# TSOC_GROVEY_I2CHUB_R2_1.net
KiCad netlist of a schematic drawn in EAGLE
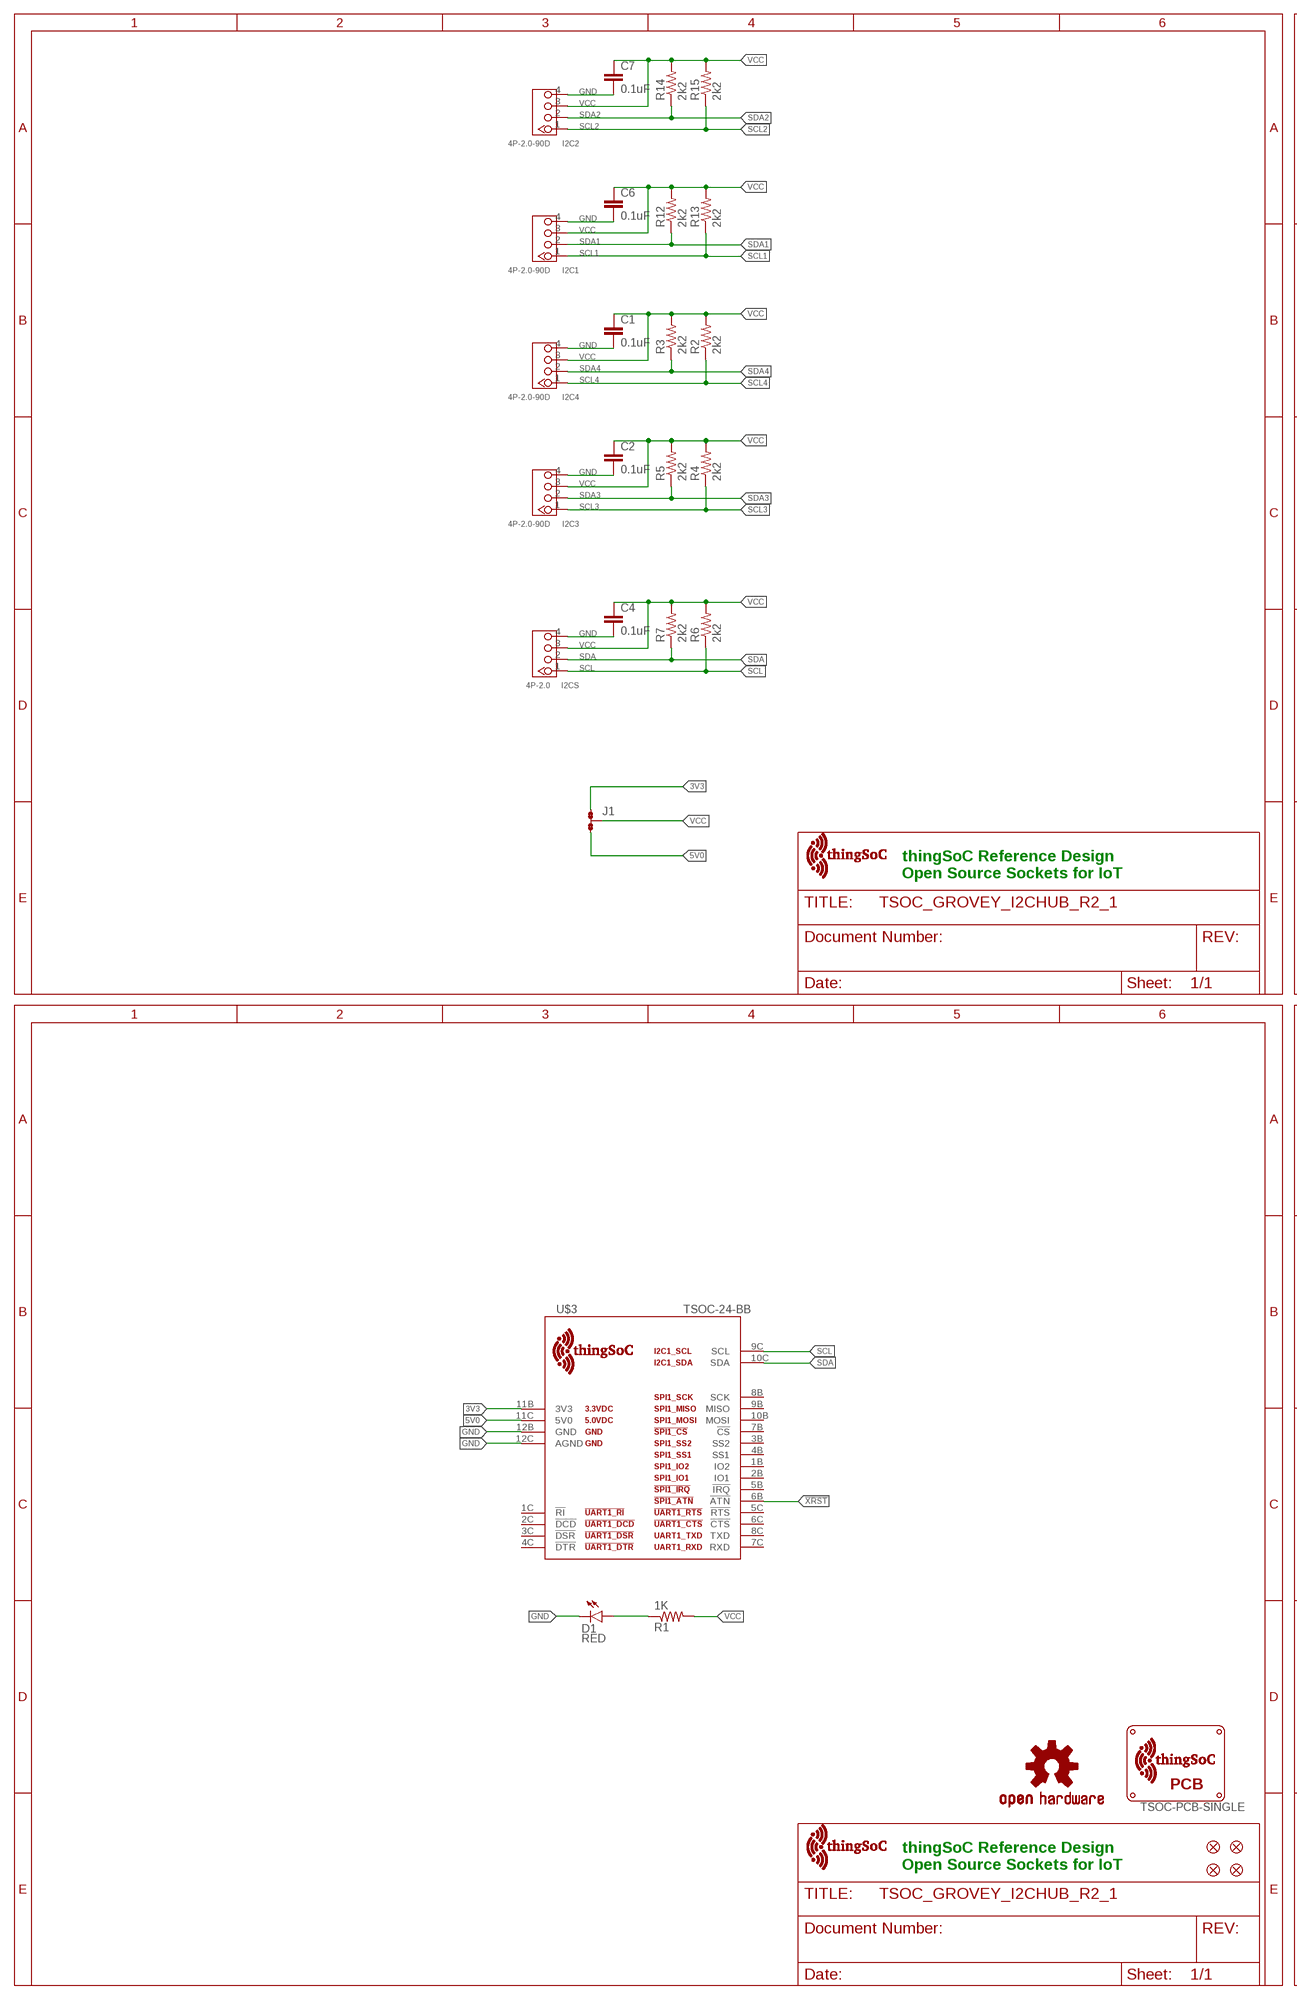
[diagram p0: schematic, sheet 1, part 1 of 2]
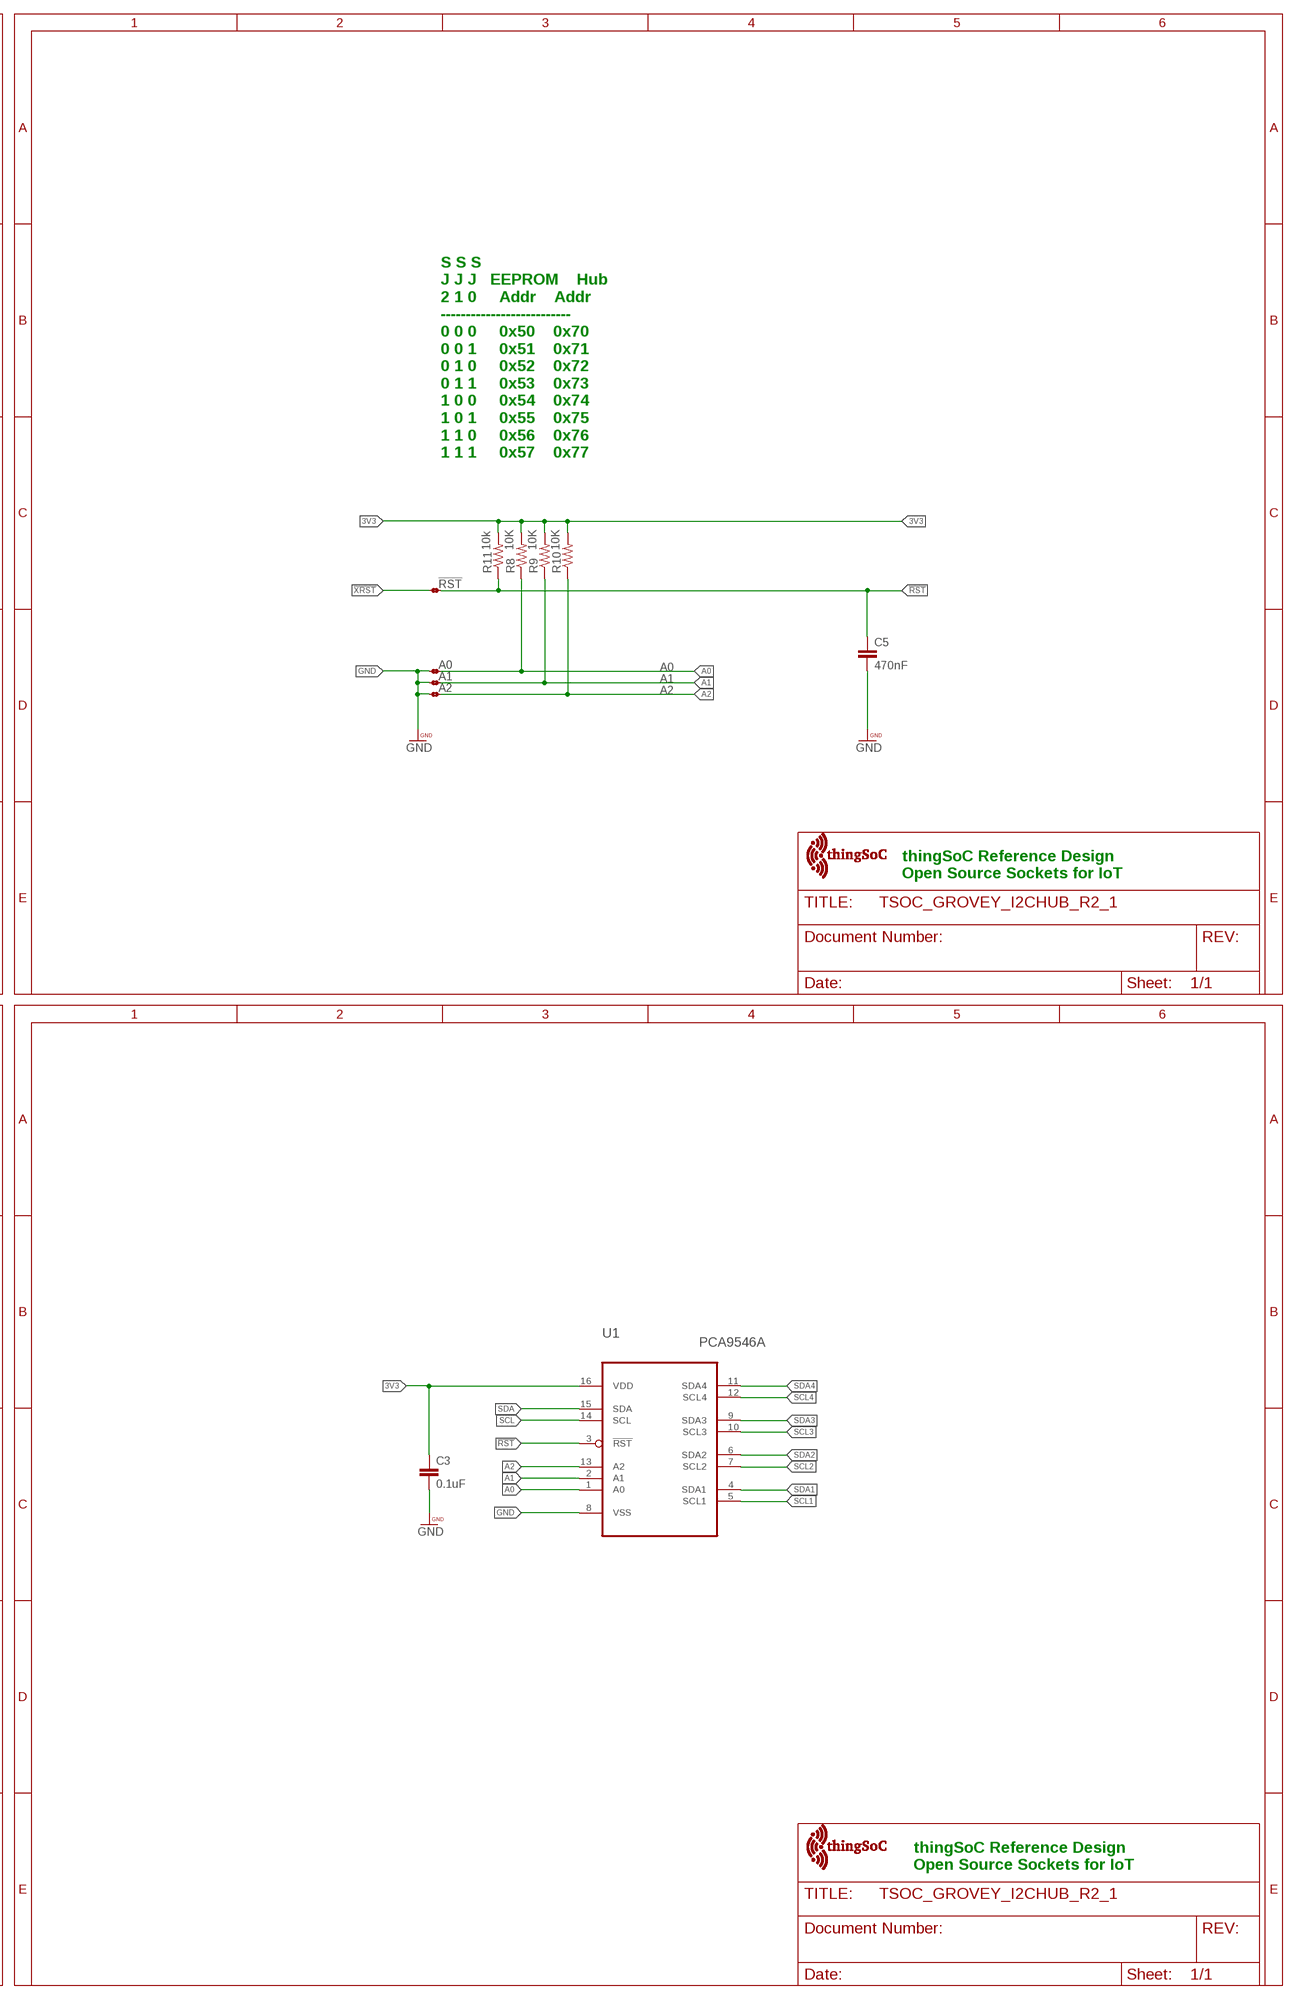
[diagram p1: schematic, sheet 1, part 2 of 2]

(export (version "E")
  (design (tool "Eeschema 10.0.6"))
  (components
    (comp (ref "!RST")
      (value "NO")
      (footprint "eagle-import:JMP-2-NO")
      (libsource (lib "eagle-import") (part "JMP-2-NO"))
    )
    (comp (ref "A0")
      (value "NO")
      (footprint "eagle-import:JMP-2-NO")
      (libsource (lib "eagle-import") (part "JMP-2-NO"))
    )
    (comp (ref "A1")
      (value "NO")
      (footprint "eagle-import:JMP-2-NO")
      (libsource (lib "eagle-import") (part "JMP-2-NO"))
    )
    (comp (ref "A2")
      (value "NO")
      (footprint "eagle-import:JMP-2-NO")
      (libsource (lib "eagle-import") (part "JMP-2-NO"))
    )
    (comp (ref "C1")
      (value "0.1uF")
      (footprint "eagle-import:0603-CAP")
      (libsource (lib "eagle-import") (part "CAP0603-CAP"))
    )
    (comp (ref "C2")
      (value "0.1uF")
      (footprint "eagle-import:0603-CAP")
      (libsource (lib "eagle-import") (part "CAP0603-CAP"))
    )
    (comp (ref "C3")
      (value "0.1uF")
      (footprint "eagle-import:0603-CAP")
      (libsource (lib "eagle-import") (part "CAP0603-CAP"))
    )
    (comp (ref "C4")
      (value "0.1uF")
      (footprint "eagle-import:0603-CAP")
      (libsource (lib "eagle-import") (part "CAP0603-CAP"))
    )
    (comp (ref "C5")
      (value "470nF")
      (footprint "eagle-import:0603-CAP")
      (libsource (lib "eagle-import") (part "CAP0603-CAP"))
    )
    (comp (ref "C6")
      (value "0.1uF")
      (footprint "eagle-import:0603-CAP")
      (libsource (lib "eagle-import") (part "CAP0603-CAP"))
    )
    (comp (ref "C7")
      (value "0.1uF")
      (footprint "eagle-import:0603-CAP")
      (libsource (lib "eagle-import") (part "CAP0603-CAP"))
    )
    (comp (ref "D1")
      (value "RED")
      (footprint "eagle-import:LED-0603")
      (libsource (lib "eagle-import") (part "LED0603"))
    )
    (comp (ref "FID1")
      (value "FIDUCIALUFIDUCIAL")
      (footprint "eagle-import:MICRO-FIDUCIAL")
      (libsource (lib "eagle-import") (part "FIDUCIALUFIDUCIAL"))
    )
    (comp (ref "FID2")
      (value "FIDUCIALUFIDUCIAL")
      (footprint "eagle-import:MICRO-FIDUCIAL")
      (libsource (lib "eagle-import") (part "FIDUCIALUFIDUCIAL"))
    )
    (comp (ref "FID3")
      (value "FIDUCIALUFIDUCIAL")
      (footprint "eagle-import:MICRO-FIDUCIAL")
      (libsource (lib "eagle-import") (part "FIDUCIALUFIDUCIAL"))
    )
    (comp (ref "FID4")
      (value "FIDUCIALUFIDUCIAL")
      (footprint "eagle-import:MICRO-FIDUCIAL")
      (libsource (lib "eagle-import") (part "FIDUCIALUFIDUCIAL"))
    )
    (comp (ref "I2C1")
      (value "4P-2.0-90D")
      (footprint "eagle-import:HW4-2.0-90D")
      (libsource (lib "eagle-import") (part "GROVE-CONNECTOR-DIP-90D(4P-2.0)"))
    )
    (comp (ref "I2C2")
      (value "4P-2.0-90D")
      (footprint "eagle-import:HW4-2.0-90D")
      (libsource (lib "eagle-import") (part "GROVE-CONNECTOR-DIP-90D(4P-2.0)"))
    )
    (comp (ref "I2C3")
      (value "4P-2.0-90D")
      (footprint "eagle-import:HW4-2.0-90D")
      (libsource (lib "eagle-import") (part "GROVE-CONNECTOR-DIP-90D(4P-2.0)"))
    )
    (comp (ref "I2C4")
      (value "4P-2.0-90D")
      (footprint "eagle-import:HW4-2.0-90D")
      (libsource (lib "eagle-import") (part "GROVE-CONNECTOR-DIP-90D(4P-2.0)"))
    )
    (comp (ref "I2CS")
      (value "4P-2.0")
      (footprint "eagle-import:HW4-2.0")
      (libsource (lib "eagle-import") (part "GROVE-CONNECTOR-DIP(4P-2.0)"))
    )
    (comp (ref "J1")
      (value "NO")
      (footprint "eagle-import:JMP-3-NO-PTH-2.54")
      (libsource (lib "eagle-import") (part "JMP-3-NO-PTH"))
    )
    (comp (ref "LOGO1")
      (value "OSHW-LOGOL")
      (footprint "eagle-import:OSHW-LOGO-L")
      (libsource (lib "eagle-import") (part "OSHW-LOGOL"))
    )
    (comp (ref "R1")
      (value "1K")
      (footprint "eagle-import:0603-RES")
      (libsource (lib "eagle-import") (part "RESISTOR_SFE0603-RES"))
    )
    (comp (ref "R2")
      (value "2k2")
      (footprint "eagle-import:0603-RES")
      (libsource (lib "eagle-import") (part "RESISTOR0603-RES"))
    )
    (comp (ref "R3")
      (value "2k2")
      (footprint "eagle-import:0603-RES")
      (libsource (lib "eagle-import") (part "RESISTOR0603-RES"))
    )
    (comp (ref "R4")
      (value "2k2")
      (footprint "eagle-import:0603-RES")
      (libsource (lib "eagle-import") (part "RESISTOR0603-RES"))
    )
    (comp (ref "R5")
      (value "2k2")
      (footprint "eagle-import:0603-RES")
      (libsource (lib "eagle-import") (part "RESISTOR0603-RES"))
    )
    (comp (ref "R6")
      (value "2k2")
      (footprint "eagle-import:0603-RES")
      (libsource (lib "eagle-import") (part "RESISTOR0603-RES"))
    )
    (comp (ref "R7")
      (value "2k2")
      (footprint "eagle-import:0603-RES")
      (libsource (lib "eagle-import") (part "RESISTOR0603-RES"))
    )
    (comp (ref "R8")
      (value "10K")
      (footprint "eagle-import:0603-RES")
      (libsource (lib "eagle-import") (part "RESISTOR0603-RES"))
    )
    (comp (ref "R9")
      (value "10K")
      (footprint "eagle-import:0603-RES")
      (libsource (lib "eagle-import") (part "RESISTOR0603-RES"))
    )
    (comp (ref "R10")
      (value "10K")
      (footprint "eagle-import:0603-RES")
      (libsource (lib "eagle-import") (part "RESISTOR0603-RES"))
    )
    (comp (ref "R11")
      (value "10k")
      (footprint "eagle-import:0603-RES")
      (libsource (lib "eagle-import") (part "RESISTOR0603-RES"))
    )
    (comp (ref "R12")
      (value "2k2")
      (footprint "eagle-import:0603-RES")
      (libsource (lib "eagle-import") (part "RESISTOR0603-RES"))
    )
    (comp (ref "R13")
      (value "2k2")
      (footprint "eagle-import:0603-RES")
      (libsource (lib "eagle-import") (part "RESISTOR0603-RES"))
    )
    (comp (ref "R14")
      (value "2k2")
      (footprint "eagle-import:0603-RES")
      (libsource (lib "eagle-import") (part "RESISTOR0603-RES"))
    )
    (comp (ref "R15")
      (value "2k2")
      (footprint "eagle-import:0603-RES")
      (libsource (lib "eagle-import") (part "RESISTOR0603-RES"))
    )
    (comp (ref "U$1")
      (value "TSOC-LOGO-SMALL")
      (footprint "eagle-import:TSOC-LOGO-SML")
      (libsource (lib "eagle-import") (part "TSOC-LOGO-SMALL"))
    )
    (comp (ref "U$2")
      (value "TSOC-PCB-SINGLE")
      (footprint "eagle-import:TSOC-BB-BRD-DIM")
      (libsource (lib "eagle-import") (part "TSOC-PCB-SINGLE"))
    )
    (comp (ref "U$3")
      (value "TSOC-24-BB")
      (footprint "eagle-import:TSOC-BB-S24")
      (libsource (lib "eagle-import") (part "TSOC-24-BB"))
    )
    (comp (ref "U$101")
      (value "TSOC-LOGO-LRG")
      (footprint "eagle-import:TSOC-LOGO-LRG")
      (libsource (lib "eagle-import") (part "TSOC-LOGO-LRG"))
    )
    (comp (ref "U$102")
      (value "TSOC-LOGO-SMALL")
      (footprint "eagle-import:TSOC-LOGO-SML")
      (libsource (lib "eagle-import") (part "TSOC-LOGO-SMALL"))
    )
    (comp (ref "U$103")
      (value "TSOC-LOGO-SMALL")
      (footprint "eagle-import:TSOC-LOGO-SML")
      (libsource (lib "eagle-import") (part "TSOC-LOGO-SMALL"))
    )
    (comp (ref "U1")
      (value "PCA9546A")
      (footprint "eagle-import:SOP65P640X110-16N")
      (fields (field (name "MPN") "PCA9546APW,112"))
      (libsource (lib "eagle-import") (part "PCA9546A"))
    )
  )
  (nets
    (net (code "1") (name "/~{RST}") (class "Default")
      (node (ref "!RST") (pin "1") (pinfunction "1_1") (pintype "passive"))
      (node (ref "C5") (pin "1") (pinfunction "1_1") (pintype "passive"))
      (node (ref "R11") (pin "1") (pinfunction "1_1") (pintype "passive"))
      (node (ref "U1") (pin "3") (pinfunction "~{RST}_3") (pintype "input"))
    )
    (net (code "2") (name "/~{XRST}") (class "Default")
      (node (ref "!RST") (pin "2") (pinfunction "2_2") (pintype "passive"))
      (node (ref "U$3") (pin "6B") (pinfunction "~{ATN}_6B") (pintype "bidirectional"))
    )
    (net (code "3") (name "3V3") (class "Default")
      (node (ref "C3") (pin "1") (pinfunction "1_1") (pintype "passive"))
      (node (ref "J1") (pin "1") (pinfunction "1_1") (pintype "passive"))
      (node (ref "R10") (pin "2") (pinfunction "2_2") (pintype "passive"))
      (node (ref "R11") (pin "2") (pinfunction "2_2") (pintype "passive"))
      (node (ref "R8") (pin "2") (pinfunction "2_2") (pintype "passive"))
      (node (ref "R9") (pin "2") (pinfunction "2_2") (pintype "passive"))
      (node (ref "U$3") (pin "11B") (pinfunction "3V3_11B") (pintype "bidirectional"))
      (node (ref "U1") (pin "16") (pinfunction "VDD_16") (pintype "power_in"))
    )
    (net (code "4") (name "5V0") (class "Default")
      (node (ref "J1") (pin "3") (pinfunction "3_3") (pintype "passive"))
      (node (ref "U$3") (pin "11C") (pinfunction "5V0_11C") (pintype "bidirectional"))
    )
    (net (code "5") (name "A0") (class "Default")
      (node (ref "A0") (pin "2") (pinfunction "2_2") (pintype "passive"))
      (node (ref "R8") (pin "1") (pinfunction "1_1") (pintype "passive"))
      (node (ref "U1") (pin "1") (pinfunction "A0_1") (pintype "input"))
    )
    (net (code "6") (name "A1") (class "Default")
      (node (ref "A1") (pin "2") (pinfunction "2_2") (pintype "passive"))
      (node (ref "R9") (pin "1") (pinfunction "1_1") (pintype "passive"))
      (node (ref "U1") (pin "2") (pinfunction "A1_2") (pintype "input"))
    )
    (net (code "7") (name "A2") (class "Default")
      (node (ref "A2") (pin "2") (pinfunction "2_2") (pintype "passive"))
      (node (ref "R10") (pin "1") (pinfunction "1_1") (pintype "passive"))
      (node (ref "U1") (pin "13") (pinfunction "A2_13") (pintype "input"))
    )
    (net (code "8") (name "GND") (class "Default")
      (node (ref "A0") (pin "1") (pinfunction "1_1") (pintype "passive"))
      (node (ref "A1") (pin "1") (pinfunction "1_1") (pintype "passive"))
      (node (ref "A2") (pin "1") (pinfunction "1_1") (pintype "passive"))
      (node (ref "C1") (pin "2") (pinfunction "2_2") (pintype "passive"))
      (node (ref "C2") (pin "2") (pinfunction "2_2") (pintype "passive"))
      (node (ref "C3") (pin "2") (pinfunction "2_2") (pintype "passive"))
      (node (ref "C4") (pin "2") (pinfunction "2_2") (pintype "passive"))
      (node (ref "C5") (pin "2") (pinfunction "2_2") (pintype "passive"))
      (node (ref "C6") (pin "2") (pinfunction "2_2") (pintype "passive"))
      (node (ref "C7") (pin "2") (pinfunction "2_2") (pintype "passive"))
      (node (ref "D1") (pin "C") (pinfunction "C_C") (pintype "passive"))
      (node (ref "I2C1") (pin "4") (pinfunction "4_4") (pintype "bidirectional"))
      (node (ref "I2C2") (pin "4") (pinfunction "4_4") (pintype "bidirectional"))
      (node (ref "I2C3") (pin "4") (pinfunction "4_4") (pintype "bidirectional"))
      (node (ref "I2C4") (pin "4") (pinfunction "4_4") (pintype "bidirectional"))
      (node (ref "I2CS") (pin "4") (pinfunction "4_4") (pintype "bidirectional"))
      (node (ref "U$3") (pin "12B") (pinfunction "GND_12B") (pintype "bidirectional"))
      (node (ref "U$3") (pin "12C") (pinfunction "AGND_12C") (pintype "bidirectional"))
      (node (ref "U1") (pin "8") (pinfunction "VSS_8") (pintype "passive"))
    )
    (net (code "9") (name "Net-(D1-PadA)") (class "Default")
      (node (ref "D1") (pin "A") (pinfunction "A_A") (pintype "passive"))
      (node (ref "R1") (pin "1") (pinfunction "1_1") (pintype "passive"))
    )
    (net (code "10") (name "SCL") (class "Default")
      (node (ref "I2CS") (pin "1") (pinfunction "1_1") (pintype "bidirectional"))
      (node (ref "R6") (pin "1") (pinfunction "1_1") (pintype "passive"))
      (node (ref "U$3") (pin "9C") (pinfunction "SCL_9C") (pintype "bidirectional"))
      (node (ref "U1") (pin "14") (pinfunction "SCL_14") (pintype "bidirectional"))
    )
    (net (code "11") (name "SCL1") (class "Default")
      (node (ref "I2C1") (pin "1") (pinfunction "1_1") (pintype "bidirectional"))
      (node (ref "R13") (pin "1") (pinfunction "1_1") (pintype "passive"))
      (node (ref "U1") (pin "5") (pinfunction "SCL1_5") (pintype "input"))
    )
    (net (code "12") (name "SCL2") (class "Default")
      (node (ref "I2C2") (pin "1") (pinfunction "1_1") (pintype "bidirectional"))
      (node (ref "R15") (pin "1") (pinfunction "1_1") (pintype "passive"))
      (node (ref "U1") (pin "7") (pinfunction "SCL2_7") (pintype "input"))
    )
    (net (code "13") (name "SCL3") (class "Default")
      (node (ref "I2C3") (pin "1") (pinfunction "1_1") (pintype "bidirectional"))
      (node (ref "R4") (pin "1") (pinfunction "1_1") (pintype "passive"))
      (node (ref "U1") (pin "10") (pinfunction "SCL3_10") (pintype "input"))
    )
    (net (code "14") (name "SCL4") (class "Default")
      (node (ref "I2C4") (pin "1") (pinfunction "1_1") (pintype "bidirectional"))
      (node (ref "R2") (pin "1") (pinfunction "1_1") (pintype "passive"))
      (node (ref "U1") (pin "12") (pinfunction "SCL4_12") (pintype "input"))
    )
    (net (code "15") (name "SDA") (class "Default")
      (node (ref "I2CS") (pin "2") (pinfunction "2_2") (pintype "bidirectional"))
      (node (ref "R7") (pin "1") (pinfunction "1_1") (pintype "passive"))
      (node (ref "U$3") (pin "10C") (pinfunction "SDA_10C") (pintype "bidirectional"))
      (node (ref "U1") (pin "15") (pinfunction "SDA_15") (pintype "bidirectional"))
    )
    (net (code "16") (name "SDA1") (class "Default")
      (node (ref "I2C1") (pin "2") (pinfunction "2_2") (pintype "bidirectional"))
      (node (ref "R12") (pin "1") (pinfunction "1_1") (pintype "passive"))
      (node (ref "U1") (pin "4") (pinfunction "SDA1_4") (pintype "input"))
    )
    (net (code "17") (name "SDA2") (class "Default")
      (node (ref "I2C2") (pin "2") (pinfunction "2_2") (pintype "bidirectional"))
      (node (ref "R14") (pin "1") (pinfunction "1_1") (pintype "passive"))
      (node (ref "U1") (pin "6") (pinfunction "SDA2_6") (pintype "input"))
    )
    (net (code "18") (name "SDA3") (class "Default")
      (node (ref "I2C3") (pin "2") (pinfunction "2_2") (pintype "bidirectional"))
      (node (ref "R5") (pin "1") (pinfunction "1_1") (pintype "passive"))
      (node (ref "U1") (pin "9") (pinfunction "SDA3_9") (pintype "input"))
    )
    (net (code "19") (name "SDA4") (class "Default")
      (node (ref "I2C4") (pin "2") (pinfunction "2_2") (pintype "bidirectional"))
      (node (ref "R3") (pin "1") (pinfunction "1_1") (pintype "passive"))
      (node (ref "U1") (pin "11") (pinfunction "SDA4_11") (pintype "input"))
    )
    (net (code "20") (name "VCC") (class "Default")
      (node (ref "C1") (pin "1") (pinfunction "1_1") (pintype "passive"))
      (node (ref "C2") (pin "1") (pinfunction "1_1") (pintype "passive"))
      (node (ref "C4") (pin "1") (pinfunction "1_1") (pintype "passive"))
      (node (ref "C6") (pin "1") (pinfunction "1_1") (pintype "passive"))
      (node (ref "C7") (pin "1") (pinfunction "1_1") (pintype "passive"))
      (node (ref "I2C1") (pin "3") (pinfunction "3_3") (pintype "bidirectional"))
      (node (ref "I2C2") (pin "3") (pinfunction "3_3") (pintype "bidirectional"))
      (node (ref "I2C3") (pin "3") (pinfunction "3_3") (pintype "bidirectional"))
      (node (ref "I2C4") (pin "3") (pinfunction "3_3") (pintype "bidirectional"))
      (node (ref "I2CS") (pin "3") (pinfunction "3_3") (pintype "bidirectional"))
      (node (ref "J1") (pin "2") (pinfunction "2_2") (pintype "passive"))
      (node (ref "R1") (pin "2") (pinfunction "2_2") (pintype "passive"))
      (node (ref "R12") (pin "2") (pinfunction "2_2") (pintype "passive"))
      (node (ref "R13") (pin "2") (pinfunction "2_2") (pintype "passive"))
      (node (ref "R14") (pin "2") (pinfunction "2_2") (pintype "passive"))
      (node (ref "R15") (pin "2") (pinfunction "2_2") (pintype "passive"))
      (node (ref "R2") (pin "2") (pinfunction "2_2") (pintype "passive"))
      (node (ref "R3") (pin "2") (pinfunction "2_2") (pintype "passive"))
      (node (ref "R4") (pin "2") (pinfunction "2_2") (pintype "passive"))
      (node (ref "R5") (pin "2") (pinfunction "2_2") (pintype "passive"))
      (node (ref "R6") (pin "2") (pinfunction "2_2") (pintype "passive"))
      (node (ref "R7") (pin "2") (pinfunction "2_2") (pintype "passive"))
    )
    (net (code "21") (name "unconnected-(U$3-IO1-Pad2B)") (class "Default")
      (node (ref "U$3") (pin "2B") (pinfunction "IO1_2B") (pintype "bidirectional"))
    )
    (net (code "22") (name "unconnected-(U$3-IO2-Pad1B)") (class "Default")
      (node (ref "U$3") (pin "1B") (pinfunction "IO2_1B") (pintype "bidirectional"))
    )
    (net (code "23") (name "unconnected-(U$3-MISO-Pad9B)") (class "Default")
      (node (ref "U$3") (pin "9B") (pinfunction "MISO_9B") (pintype "bidirectional"))
    )
    (net (code "24") (name "unconnected-(U$3-MOSI-Pad10B)") (class "Default")
      (node (ref "U$3") (pin "10B") (pinfunction "MOSI_10B") (pintype "bidirectional"))
    )
    (net (code "25") (name "unconnected-(U$3-RXD-Pad7C)") (class "Default")
      (node (ref "U$3") (pin "7C") (pinfunction "RXD_7C") (pintype "bidirectional"))
    )
    (net (code "26") (name "unconnected-(U$3-SCK-Pad8B)") (class "Default")
      (node (ref "U$3") (pin "8B") (pinfunction "SCK_8B") (pintype "bidirectional"))
    )
    (net (code "27") (name "unconnected-(U$3-SS1-Pad4B)") (class "Default")
      (node (ref "U$3") (pin "4B") (pinfunction "SS1_4B") (pintype "bidirectional"))
    )
    (net (code "28") (name "unconnected-(U$3-SS2-Pad3B)") (class "Default")
      (node (ref "U$3") (pin "3B") (pinfunction "SS2_3B") (pintype "bidirectional"))
    )
    (net (code "29") (name "unconnected-(U$3-TXD-Pad8C)") (class "Default")
      (node (ref "U$3") (pin "8C") (pinfunction "TXD_8C") (pintype "bidirectional"))
    )
    (net (code "30") (name "unconnected-(U$3-~{CS}-Pad7B)") (class "Default")
      (node (ref "U$3") (pin "7B") (pinfunction "~{CS}_7B") (pintype "bidirectional"))
    )
    (net (code "31") (name "unconnected-(U$3-~{CTS}-Pad6C)") (class "Default")
      (node (ref "U$3") (pin "6C") (pinfunction "~{CTS}_6C") (pintype "bidirectional"))
    )
    (net (code "32") (name "unconnected-(U$3-~{DCD}-Pad2C)") (class "Default")
      (node (ref "U$3") (pin "2C") (pinfunction "~{DCD}_2C") (pintype "bidirectional"))
    )
    (net (code "33") (name "unconnected-(U$3-~{DSR}-Pad3C)") (class "Default")
      (node (ref "U$3") (pin "3C") (pinfunction "~{DSR}_3C") (pintype "bidirectional"))
    )
    (net (code "34") (name "unconnected-(U$3-~{DTR}-Pad4C)") (class "Default")
      (node (ref "U$3") (pin "4C") (pinfunction "~{DTR}_4C") (pintype "bidirectional"))
    )
    (net (code "35") (name "unconnected-(U$3-~{IRQ}-Pad5B)") (class "Default")
      (node (ref "U$3") (pin "5B") (pinfunction "~{IRQ}_5B") (pintype "bidirectional"))
    )
    (net (code "36") (name "unconnected-(U$3-~{RI}-Pad1C)") (class "Default")
      (node (ref "U$3") (pin "1C") (pinfunction "~{RI}_1C") (pintype "bidirectional"))
    )
    (net (code "37") (name "unconnected-(U$3-~{RTS}-Pad5C)") (class "Default")
      (node (ref "U$3") (pin "5C") (pinfunction "~{RTS}_5C") (pintype "bidirectional"))
    )
  )
)
